# OLED.net
KiCad netlist of a schematic drawn in Altium Designer
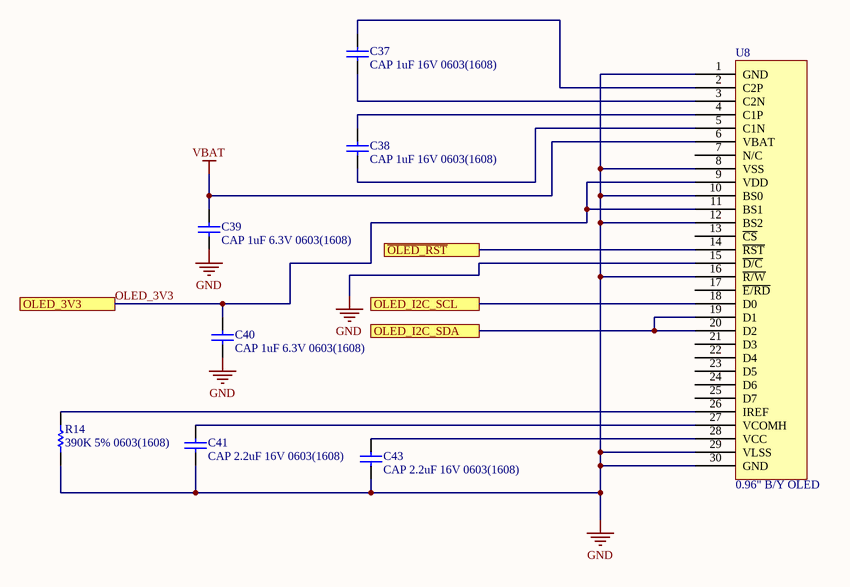
[diagram p0: OLED.SchDoc]

(export (version "E")
  (design (tool "Eeschema 10.0.6"))
  (components
    (comp (ref "C37")
      (value "CAP 1uF 16V 0603(1608)")
      (footprint "CAPC0603(1608)100_L")
      (description "CAP 1uF 16V ±20% 0603 (1608 Metric) Thickness 1mm SMD")
      (fields (field (name "TOLERANCE") "Â±20%"))
      (libsource (lib "Altium Content Vault") (part "CAP"))
    )
    (comp (ref "C38")
      (value "CAP 1uF 16V 0603(1608)")
      (footprint "CAPC0603(1608)100_L")
      (description "CAP 1uF 16V ±20% 0603 (1608 Metric) Thickness 1mm SMD")
      (fields (field (name "TOLERANCE") "Â±20%"))
      (libsource (lib "Altium Content Vault") (part "CAP"))
    )
    (comp (ref "C39")
      (value "CAP 1uF 6.3V 0603(1608)")
      (footprint "CAPC0603(1608)100_L")
      (description "CAP 1uF 6.3V ±20% 0603 (1608 Metric) Thickness 1mm SMD")
      (fields (field (name "TOLERANCE") "Â±20%"))
      (libsource (lib "Altium Content Vault") (part "CAP"))
    )
    (comp (ref "C40")
      (value "CAP 1uF 6.3V 0603(1608)")
      (footprint "CAPC0603(1608)100_L")
      (description "CAP 1uF 6.3V ±20% 0603 (1608 Metric) Thickness 1mm SMD")
      (fields (field (name "TOLERANCE") "Â±20%"))
      (libsource (lib "Altium Content Vault") (part "CAP"))
    )
    (comp (ref "C41")
      (value "CAP 2.2uF 16V 0603(1608)")
      (footprint "CAPC0603(1608)55_L")
      (description "CAP 2.2uF 16V ±20% 0603 (1608 Metric) Thickness 0.55mm SMD")
      (fields (field (name "TOLERANCE") "Â±20%"))
      (libsource (lib "Altium Content Vault") (part "CAP"))
    )
    (comp (ref "C43")
      (value "CAP 2.2uF 16V 0603(1608)")
      (footprint "CAPC0603(1608)55_L")
      (description "CAP 2.2uF 16V ±20% 0603 (1608 Metric) Thickness 0.55mm SMD")
      (fields (field (name "TOLERANCE") "Â±20%"))
      (libsource (lib "Altium Content Vault") (part "CAP"))
    )
    (comp (ref "R14")
      (value "390K 5% 0603(1608)")
      (footprint "RESC0603(1608)_N")
      (description "390K 0.1W 5% 0603 (1608 Metric)  SMD")
      (fields (field (name "POWER") "0.1 W") (field (name "TOLERANCE") "5 %"))
      (libsource (lib "Altium Content Vault") (part "RES"))
    )
    (comp (ref "U8")
      (value "0.96\" B/Y OLED")
      (footprint "0.96\" B/Y OLED")
      (description "0.96\" Blue/Yellow OLED 128x64 SSD1306")
      (libsource (lib "Parts") (part "0.96{dblquote} B/Y OLED"))
    )
  )
  (nets
    (net (code "1") (name "/OLED_3V3") (class "Default")
      (node (ref "C40") (pin "2") (pinfunction "2_2") (pintype "passive"))
      (node (ref "U8") (pin "11") (pinfunction "BS1_11") (pintype "passive"))
      (node (ref "U8") (pin "9") (pinfunction "VDD_9") (pintype "passive"))
    )
    (net (code "2") (name "/OLED_I2C_SCL") (class "Default")
      (node (ref "U8") (pin "18") (pinfunction "D0_18") (pintype "passive"))
    )
    (net (code "3") (name "/OLED_I2C_SDA") (class "Default")
      (node (ref "U8") (pin "19") (pinfunction "D1_19") (pintype "passive"))
      (node (ref "U8") (pin "20") (pinfunction "D2_20") (pintype "passive"))
    )
    (net (code "4") (name "/OLED_RST") (class "Default")
      (node (ref "U8") (pin "14") (pinfunction "RST_14") (pintype "passive"))
    )
    (net (code "5") (name "GND") (class "Default")
      (node (ref "C39") (pin "1") (pinfunction "1_1") (pintype "passive"))
      (node (ref "C40") (pin "1") (pinfunction "1_1") (pintype "passive"))
      (node (ref "C41") (pin "1") (pinfunction "1_1") (pintype "passive"))
      (node (ref "C43") (pin "1") (pinfunction "1_1") (pintype "passive"))
      (node (ref "R14") (pin "1") (pinfunction "1_1") (pintype "passive"))
      (node (ref "U8") (pin "1") (pinfunction "GND_1") (pintype "passive"))
      (node (ref "U8") (pin "10") (pinfunction "BS0_10") (pintype "passive"))
      (node (ref "U8") (pin "12") (pinfunction "BS2_12") (pintype "passive"))
      (node (ref "U8") (pin "15") (pinfunction "D/C_15") (pintype "passive"))
      (node (ref "U8") (pin "16") (pinfunction "R/W_16") (pintype "passive"))
      (node (ref "U8") (pin "29") (pinfunction "VLSS_29") (pintype "passive"))
      (node (ref "U8") (pin "30") (pinfunction "GND_30") (pintype "passive"))
      (node (ref "U8") (pin "8") (pinfunction "VSS_8") (pintype "passive"))
    )
    (net (code "6") (name "Net-(U8-C1N)") (class "Default")
      (node (ref "C38") (pin "1") (pinfunction "1_1") (pintype "passive"))
      (node (ref "U8") (pin "5") (pinfunction "C1N_5") (pintype "passive"))
    )
    (net (code "7") (name "Net-(U8-C1P)") (class "Default")
      (node (ref "C38") (pin "2") (pinfunction "2_2") (pintype "passive"))
      (node (ref "U8") (pin "4") (pinfunction "C1P_4") (pintype "passive"))
    )
    (net (code "8") (name "Net-(U8-C2N)") (class "Default")
      (node (ref "C37") (pin "1") (pinfunction "1_1") (pintype "passive"))
      (node (ref "U8") (pin "3") (pinfunction "C2N_3") (pintype "passive"))
    )
    (net (code "9") (name "Net-(U8-C2P)") (class "Default")
      (node (ref "C37") (pin "2") (pinfunction "2_2") (pintype "passive"))
      (node (ref "U8") (pin "2") (pinfunction "C2P_2") (pintype "passive"))
    )
    (net (code "10") (name "Net-(U8-IREF)") (class "Default")
      (node (ref "R14") (pin "2") (pinfunction "2_2") (pintype "passive"))
      (node (ref "U8") (pin "26") (pinfunction "IREF_26") (pintype "passive"))
    )
    (net (code "11") (name "Net-(U8-VCC)") (class "Default")
      (node (ref "C43") (pin "2") (pinfunction "2_2") (pintype "passive"))
      (node (ref "U8") (pin "28") (pinfunction "VCC_28") (pintype "passive"))
    )
    (net (code "12") (name "Net-(U8-VCOMH)") (class "Default")
      (node (ref "C41") (pin "2") (pinfunction "2_2") (pintype "passive"))
      (node (ref "U8") (pin "27") (pinfunction "VCOMH_27") (pintype "passive"))
    )
    (net (code "13") (name "VBAT") (class "Default")
      (node (ref "C39") (pin "2") (pinfunction "2_2") (pintype "passive"))
      (node (ref "U8") (pin "6") (pinfunction "VBAT_6") (pintype "passive"))
    )
    (net (code "14") (name "unconnected-(U8-CS-Pad13)") (class "Default")
      (node (ref "U8") (pin "13") (pinfunction "CS_13") (pintype "passive"))
    )
    (net (code "15") (name "unconnected-(U8-D3-Pad21)") (class "Default")
      (node (ref "U8") (pin "21") (pinfunction "D3_21") (pintype "passive"))
    )
    (net (code "16") (name "unconnected-(U8-D4-Pad22)") (class "Default")
      (node (ref "U8") (pin "22") (pinfunction "D4_22") (pintype "passive"))
    )
    (net (code "17") (name "unconnected-(U8-D5-Pad23)") (class "Default")
      (node (ref "U8") (pin "23") (pinfunction "D5_23") (pintype "passive"))
    )
    (net (code "18") (name "unconnected-(U8-D6-Pad24)") (class "Default")
      (node (ref "U8") (pin "24") (pinfunction "D6_24") (pintype "passive"))
    )
    (net (code "19") (name "unconnected-(U8-D7-Pad25)") (class "Default")
      (node (ref "U8") (pin "25") (pinfunction "D7_25") (pintype "passive"))
    )
    (net (code "20") (name "unconnected-(U8-E{slash}RD-Pad17)") (class "Default")
      (node (ref "U8") (pin "17") (pinfunction "E/RD_17") (pintype "passive"))
    )
    (net (code "21") (name "unconnected-(U8-N{slash}C-Pad7)") (class "Default")
      (node (ref "U8") (pin "7") (pinfunction "N/C_7") (pintype "passive"))
    )
  )
)
